# sd_card.net
KiCad netlist of a schematic drawn in Altium Designer
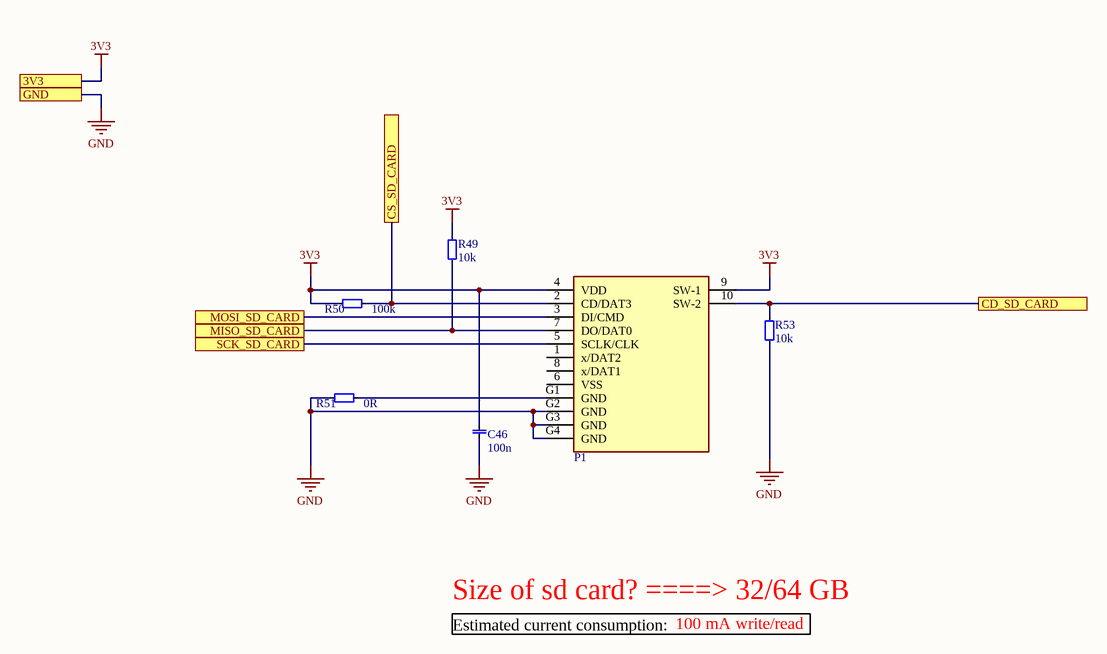
[diagram p0: sd_card.SchDoc]

(export (version "E")
  (design (tool "Eeschema 10.0.6"))
  (components
    (comp (ref "C46")
      (value "100n")
      (footprint "0402 CAP")
      (fields
        (field (name "MANUFACTURER PART NO") "GRM155R62A104KE14D")
        (field (name "Comment") "0603, capacitor")
      )
      (libsource (lib "jclib") (part "0603, capacitor"))
    )
    (comp (ref "P1")
      (value "SD Card connector")
      (footprint "MOLEX_104031-0811")
      (description "SD Card connector - SD Card connector")
      (fields (field (name "MANUFACTURER PART NO") "1040310811"))
      (libsource (lib "urad") (part "SD Card connector"))
    )
    (comp (ref "R49")
      (value "10k")
      (footprint "0402 res")
      (fields
        (field (name "MANUFACTURER PART NO") "311-10.0KLRCT-ND")
        (field (name "Comment") "0603, resistor")
      )
      (libsource (lib "jclib") (part "0603, resistor"))
    )
    (comp (ref "R50")
      (value "100k")
      (footprint "0402 res")
      (fields
        (field (name "MANUFACTURER PART NO") "RC0402FR-07100KL")
        (field (name "Comment") "0603, resistor")
      )
      (libsource (lib "jclib") (part "0603, resistor"))
    )
    (comp (ref "R51")
      (value "0R")
      (footprint "0402 res")
      (fields
        (field (name "MANUFACTURER PART NO") "RMCF0402ZT0R00")
        (field (name "Comment") "0603, resistor")
      )
      (libsource (lib "jclib") (part "0603, resistor"))
    )
    (comp (ref "R53")
      (value "10k")
      (footprint "0402 res")
      (fields
        (field (name "MANUFACTURER PART NO") "311-10.0KLRCT-ND")
        (field (name "Comment") "0603, resistor")
      )
      (libsource (lib "jclib") (part "0603, resistor"))
    )
  )
  (nets
    (net (code "1") (name "/CD_SD_CARD") (class "Default")
      (node (ref "P1") (pin "10") (pinfunction "SW-2_10") (pintype "passive"))
      (node (ref "R53") (pin "0") (pinfunction "0_0") (pintype "passive"))
    )
    (net (code "2") (name "/CS_SD_CARD") (class "Default")
      (node (ref "P1") (pin "2") (pinfunction "CD/DAT3_2") (pintype "passive"))
      (node (ref "R50") (pin "1") (pinfunction "1_1") (pintype "passive"))
    )
    (net (code "3") (name "/MISO_SD_CARD") (class "Default")
      (node (ref "P1") (pin "7") (pinfunction "DO/DAT0_7") (pintype "passive"))
      (node (ref "R49") (pin "1") (pinfunction "1_1") (pintype "passive"))
    )
    (net (code "4") (name "/MOSI_SD_CARD") (class "Default")
      (node (ref "P1") (pin "3") (pinfunction "DI/CMD_3") (pintype "passive"))
    )
    (net (code "5") (name "/SCK_SD_CARD") (class "Default")
      (node (ref "P1") (pin "5") (pinfunction "SCLK/CLK_5") (pintype "passive"))
    )
    (net (code "6") (name "3V3") (class "Default")
      (node (ref "C46") (pin "1") (pinfunction "1_1") (pintype "passive"))
      (node (ref "P1") (pin "4") (pinfunction "VDD_4") (pintype "power_in"))
      (node (ref "P1") (pin "9") (pinfunction "SW-1_9") (pintype "passive"))
      (node (ref "R49") (pin "0") (pinfunction "0_0") (pintype "passive"))
      (node (ref "R50") (pin "0") (pinfunction "0_0") (pintype "passive"))
    )
    (net (code "7") (name "GND") (class "Default")
      (node (ref "C46") (pin "0") (pinfunction "0_0") (pintype "passive"))
      (node (ref "P1") (pin "G2") (pinfunction "GND_G2") (pintype "power_in"))
      (node (ref "P1") (pin "G3") (pinfunction "GND_G3") (pintype "power_in"))
      (node (ref "P1") (pin "G4") (pinfunction "GND_G4") (pintype "power_in"))
      (node (ref "R51") (pin "0") (pinfunction "0_0") (pintype "passive"))
      (node (ref "R53") (pin "1") (pinfunction "1_1") (pintype "passive"))
    )
    (net (code "8") (name "Net-(P1-GND-PadG1)") (class "Default")
      (node (ref "P1") (pin "G1") (pinfunction "GND_G1") (pintype "power_in"))
      (node (ref "R51") (pin "1") (pinfunction "1_1") (pintype "passive"))
    )
    (net (code "9") (name "unconnected-(P1-VSS-Pad6)") (class "Default")
      (node (ref "P1") (pin "6") (pinfunction "VSS_6") (pintype "power_in"))
    )
    (net (code "10") (name "unconnected-(P1-x{slash}DAT1-Pad8)") (class "Default")
      (node (ref "P1") (pin "8") (pinfunction "x/DAT1_8") (pintype "passive"))
    )
    (net (code "11") (name "unconnected-(P1-x{slash}DAT2-Pad1)") (class "Default")
      (node (ref "P1") (pin "1") (pinfunction "x/DAT2_1") (pintype "passive"))
    )
  )
)
